# PixieChroma.net
KiCad netlist of a schematic drawn in EAGLE
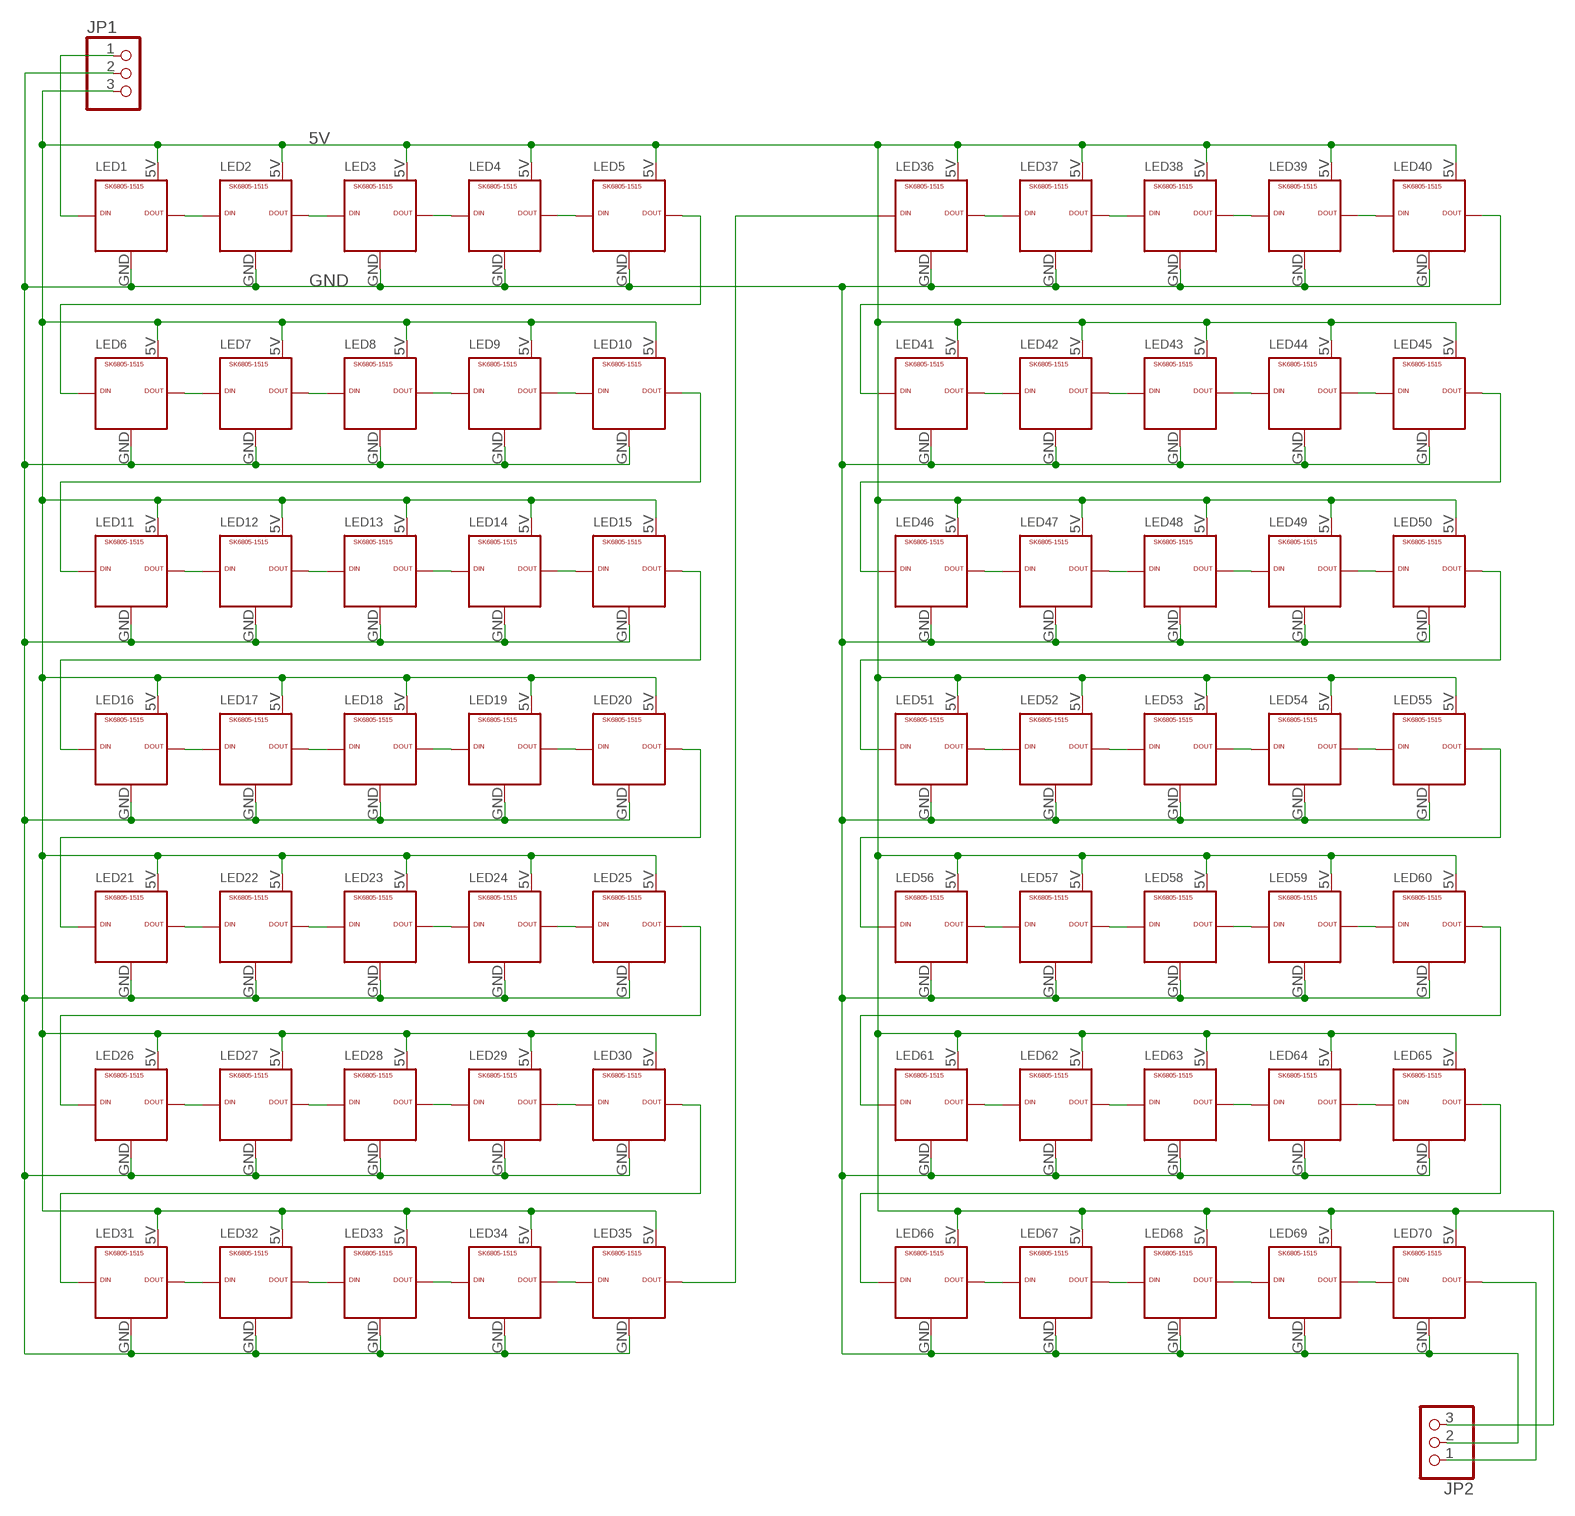
[diagram p0: schematic, sheet 1]

(export (version "E")
  (design (tool "Eeschema 10.0.6"))
  (components
    (comp (ref "JP1")
      (value "PINHD-1X3")
      (footprint "eagle-import:1X03")
      (libsource (lib "eagle-import") (part "PINHD-1X3"))
    )
    (comp (ref "JP2")
      (value "PINHD-1X3")
      (footprint "eagle-import:1X03")
      (libsource (lib "eagle-import") (part "PINHD-1X3"))
    )
    (comp (ref "LED1")
      (value "SK6805-1515")
      (footprint "eagle-import:1515")
      (libsource (lib "eagle-import") (part "SK6805-1515"))
    )
    (comp (ref "LED2")
      (value "SK6805-1515")
      (footprint "eagle-import:1515")
      (libsource (lib "eagle-import") (part "SK6805-1515"))
    )
    (comp (ref "LED3")
      (value "SK6805-1515")
      (footprint "eagle-import:1515")
      (libsource (lib "eagle-import") (part "SK6805-1515"))
    )
    (comp (ref "LED4")
      (value "SK6805-1515")
      (footprint "eagle-import:1515")
      (libsource (lib "eagle-import") (part "SK6805-1515"))
    )
    (comp (ref "LED5")
      (value "SK6805-1515")
      (footprint "eagle-import:1515")
      (libsource (lib "eagle-import") (part "SK6805-1515"))
    )
    (comp (ref "LED6")
      (value "SK6805-1515")
      (footprint "eagle-import:1515")
      (libsource (lib "eagle-import") (part "SK6805-1515"))
    )
    (comp (ref "LED7")
      (value "SK6805-1515")
      (footprint "eagle-import:1515")
      (libsource (lib "eagle-import") (part "SK6805-1515"))
    )
    (comp (ref "LED8")
      (value "SK6805-1515")
      (footprint "eagle-import:1515")
      (libsource (lib "eagle-import") (part "SK6805-1515"))
    )
    (comp (ref "LED9")
      (value "SK6805-1515")
      (footprint "eagle-import:1515")
      (libsource (lib "eagle-import") (part "SK6805-1515"))
    )
    (comp (ref "LED10")
      (value "SK6805-1515")
      (footprint "eagle-import:1515")
      (libsource (lib "eagle-import") (part "SK6805-1515"))
    )
    (comp (ref "LED11")
      (value "SK6805-1515")
      (footprint "eagle-import:1515")
      (libsource (lib "eagle-import") (part "SK6805-1515"))
    )
    (comp (ref "LED12")
      (value "SK6805-1515")
      (footprint "eagle-import:1515")
      (libsource (lib "eagle-import") (part "SK6805-1515"))
    )
    (comp (ref "LED13")
      (value "SK6805-1515")
      (footprint "eagle-import:1515")
      (libsource (lib "eagle-import") (part "SK6805-1515"))
    )
    (comp (ref "LED14")
      (value "SK6805-1515")
      (footprint "eagle-import:1515")
      (libsource (lib "eagle-import") (part "SK6805-1515"))
    )
    (comp (ref "LED15")
      (value "SK6805-1515")
      (footprint "eagle-import:1515")
      (libsource (lib "eagle-import") (part "SK6805-1515"))
    )
    (comp (ref "LED16")
      (value "SK6805-1515")
      (footprint "eagle-import:1515")
      (libsource (lib "eagle-import") (part "SK6805-1515"))
    )
    (comp (ref "LED17")
      (value "SK6805-1515")
      (footprint "eagle-import:1515")
      (libsource (lib "eagle-import") (part "SK6805-1515"))
    )
    (comp (ref "LED18")
      (value "SK6805-1515")
      (footprint "eagle-import:1515")
      (libsource (lib "eagle-import") (part "SK6805-1515"))
    )
    (comp (ref "LED19")
      (value "SK6805-1515")
      (footprint "eagle-import:1515")
      (libsource (lib "eagle-import") (part "SK6805-1515"))
    )
    (comp (ref "LED20")
      (value "SK6805-1515")
      (footprint "eagle-import:1515")
      (libsource (lib "eagle-import") (part "SK6805-1515"))
    )
    (comp (ref "LED21")
      (value "SK6805-1515")
      (footprint "eagle-import:1515")
      (libsource (lib "eagle-import") (part "SK6805-1515"))
    )
    (comp (ref "LED22")
      (value "SK6805-1515")
      (footprint "eagle-import:1515")
      (libsource (lib "eagle-import") (part "SK6805-1515"))
    )
    (comp (ref "LED23")
      (value "SK6805-1515")
      (footprint "eagle-import:1515")
      (libsource (lib "eagle-import") (part "SK6805-1515"))
    )
    (comp (ref "LED24")
      (value "SK6805-1515")
      (footprint "eagle-import:1515")
      (libsource (lib "eagle-import") (part "SK6805-1515"))
    )
    (comp (ref "LED25")
      (value "SK6805-1515")
      (footprint "eagle-import:1515")
      (libsource (lib "eagle-import") (part "SK6805-1515"))
    )
    (comp (ref "LED26")
      (value "SK6805-1515")
      (footprint "eagle-import:1515")
      (libsource (lib "eagle-import") (part "SK6805-1515"))
    )
    (comp (ref "LED27")
      (value "SK6805-1515")
      (footprint "eagle-import:1515")
      (libsource (lib "eagle-import") (part "SK6805-1515"))
    )
    (comp (ref "LED28")
      (value "SK6805-1515")
      (footprint "eagle-import:1515")
      (libsource (lib "eagle-import") (part "SK6805-1515"))
    )
    (comp (ref "LED29")
      (value "SK6805-1515")
      (footprint "eagle-import:1515")
      (libsource (lib "eagle-import") (part "SK6805-1515"))
    )
    (comp (ref "LED30")
      (value "SK6805-1515")
      (footprint "eagle-import:1515")
      (libsource (lib "eagle-import") (part "SK6805-1515"))
    )
    (comp (ref "LED31")
      (value "SK6805-1515")
      (footprint "eagle-import:1515")
      (libsource (lib "eagle-import") (part "SK6805-1515"))
    )
    (comp (ref "LED32")
      (value "SK6805-1515")
      (footprint "eagle-import:1515")
      (libsource (lib "eagle-import") (part "SK6805-1515"))
    )
    (comp (ref "LED33")
      (value "SK6805-1515")
      (footprint "eagle-import:1515")
      (libsource (lib "eagle-import") (part "SK6805-1515"))
    )
    (comp (ref "LED34")
      (value "SK6805-1515")
      (footprint "eagle-import:1515")
      (libsource (lib "eagle-import") (part "SK6805-1515"))
    )
    (comp (ref "LED35")
      (value "SK6805-1515")
      (footprint "eagle-import:1515")
      (libsource (lib "eagle-import") (part "SK6805-1515"))
    )
    (comp (ref "LED36")
      (value "SK6805-1515")
      (footprint "eagle-import:1515")
      (libsource (lib "eagle-import") (part "SK6805-1515"))
    )
    (comp (ref "LED37")
      (value "SK6805-1515")
      (footprint "eagle-import:1515")
      (libsource (lib "eagle-import") (part "SK6805-1515"))
    )
    (comp (ref "LED38")
      (value "SK6805-1515")
      (footprint "eagle-import:1515")
      (libsource (lib "eagle-import") (part "SK6805-1515"))
    )
    (comp (ref "LED39")
      (value "SK6805-1515")
      (footprint "eagle-import:1515")
      (libsource (lib "eagle-import") (part "SK6805-1515"))
    )
    (comp (ref "LED40")
      (value "SK6805-1515")
      (footprint "eagle-import:1515")
      (libsource (lib "eagle-import") (part "SK6805-1515"))
    )
    (comp (ref "LED41")
      (value "SK6805-1515")
      (footprint "eagle-import:1515")
      (libsource (lib "eagle-import") (part "SK6805-1515"))
    )
    (comp (ref "LED42")
      (value "SK6805-1515")
      (footprint "eagle-import:1515")
      (libsource (lib "eagle-import") (part "SK6805-1515"))
    )
    (comp (ref "LED43")
      (value "SK6805-1515")
      (footprint "eagle-import:1515")
      (libsource (lib "eagle-import") (part "SK6805-1515"))
    )
    (comp (ref "LED44")
      (value "SK6805-1515")
      (footprint "eagle-import:1515")
      (libsource (lib "eagle-import") (part "SK6805-1515"))
    )
    (comp (ref "LED45")
      (value "SK6805-1515")
      (footprint "eagle-import:1515")
      (libsource (lib "eagle-import") (part "SK6805-1515"))
    )
    (comp (ref "LED46")
      (value "SK6805-1515")
      (footprint "eagle-import:1515")
      (libsource (lib "eagle-import") (part "SK6805-1515"))
    )
    (comp (ref "LED47")
      (value "SK6805-1515")
      (footprint "eagle-import:1515")
      (libsource (lib "eagle-import") (part "SK6805-1515"))
    )
    (comp (ref "LED48")
      (value "SK6805-1515")
      (footprint "eagle-import:1515")
      (libsource (lib "eagle-import") (part "SK6805-1515"))
    )
    (comp (ref "LED49")
      (value "SK6805-1515")
      (footprint "eagle-import:1515")
      (libsource (lib "eagle-import") (part "SK6805-1515"))
    )
    (comp (ref "LED50")
      (value "SK6805-1515")
      (footprint "eagle-import:1515")
      (libsource (lib "eagle-import") (part "SK6805-1515"))
    )
    (comp (ref "LED51")
      (value "SK6805-1515")
      (footprint "eagle-import:1515")
      (libsource (lib "eagle-import") (part "SK6805-1515"))
    )
    (comp (ref "LED52")
      (value "SK6805-1515")
      (footprint "eagle-import:1515")
      (libsource (lib "eagle-import") (part "SK6805-1515"))
    )
    (comp (ref "LED53")
      (value "SK6805-1515")
      (footprint "eagle-import:1515")
      (libsource (lib "eagle-import") (part "SK6805-1515"))
    )
    (comp (ref "LED54")
      (value "SK6805-1515")
      (footprint "eagle-import:1515")
      (libsource (lib "eagle-import") (part "SK6805-1515"))
    )
    (comp (ref "LED55")
      (value "SK6805-1515")
      (footprint "eagle-import:1515")
      (libsource (lib "eagle-import") (part "SK6805-1515"))
    )
    (comp (ref "LED56")
      (value "SK6805-1515")
      (footprint "eagle-import:1515")
      (libsource (lib "eagle-import") (part "SK6805-1515"))
    )
    (comp (ref "LED57")
      (value "SK6805-1515")
      (footprint "eagle-import:1515")
      (libsource (lib "eagle-import") (part "SK6805-1515"))
    )
    (comp (ref "LED58")
      (value "SK6805-1515")
      (footprint "eagle-import:1515")
      (libsource (lib "eagle-import") (part "SK6805-1515"))
    )
    (comp (ref "LED59")
      (value "SK6805-1515")
      (footprint "eagle-import:1515")
      (libsource (lib "eagle-import") (part "SK6805-1515"))
    )
    (comp (ref "LED60")
      (value "SK6805-1515")
      (footprint "eagle-import:1515")
      (libsource (lib "eagle-import") (part "SK6805-1515"))
    )
    (comp (ref "LED61")
      (value "SK6805-1515")
      (footprint "eagle-import:1515")
      (libsource (lib "eagle-import") (part "SK6805-1515"))
    )
    (comp (ref "LED62")
      (value "SK6805-1515")
      (footprint "eagle-import:1515")
      (libsource (lib "eagle-import") (part "SK6805-1515"))
    )
    (comp (ref "LED63")
      (value "SK6805-1515")
      (footprint "eagle-import:1515")
      (libsource (lib "eagle-import") (part "SK6805-1515"))
    )
    (comp (ref "LED64")
      (value "SK6805-1515")
      (footprint "eagle-import:1515")
      (libsource (lib "eagle-import") (part "SK6805-1515"))
    )
    (comp (ref "LED65")
      (value "SK6805-1515")
      (footprint "eagle-import:1515")
      (libsource (lib "eagle-import") (part "SK6805-1515"))
    )
    (comp (ref "LED66")
      (value "SK6805-1515")
      (footprint "eagle-import:1515")
      (libsource (lib "eagle-import") (part "SK6805-1515"))
    )
    (comp (ref "LED67")
      (value "SK6805-1515")
      (footprint "eagle-import:1515")
      (libsource (lib "eagle-import") (part "SK6805-1515"))
    )
    (comp (ref "LED68")
      (value "SK6805-1515")
      (footprint "eagle-import:1515")
      (libsource (lib "eagle-import") (part "SK6805-1515"))
    )
    (comp (ref "LED69")
      (value "SK6805-1515")
      (footprint "eagle-import:1515")
      (libsource (lib "eagle-import") (part "SK6805-1515"))
    )
    (comp (ref "LED70")
      (value "SK6805-1515")
      (footprint "eagle-import:1515")
      (libsource (lib "eagle-import") (part "SK6805-1515"))
    )
  )
  (nets
    (net (code "1") (name "/5V") (class "Default")
      (node (ref "JP1") (pin "3") (pinfunction "3_3") (pintype "passive"))
      (node (ref "JP2") (pin "3") (pinfunction "3_3") (pintype "passive"))
      (node (ref "LED1") (pin "5V") (pinfunction "5V_5V") (pintype "power_in"))
      (node (ref "LED10") (pin "5V") (pinfunction "5V_5V") (pintype "power_in"))
      (node (ref "LED11") (pin "5V") (pinfunction "5V_5V") (pintype "power_in"))
      (node (ref "LED12") (pin "5V") (pinfunction "5V_5V") (pintype "power_in"))
      (node (ref "LED13") (pin "5V") (pinfunction "5V_5V") (pintype "power_in"))
      (node (ref "LED14") (pin "5V") (pinfunction "5V_5V") (pintype "power_in"))
      (node (ref "LED15") (pin "5V") (pinfunction "5V_5V") (pintype "power_in"))
      (node (ref "LED16") (pin "5V") (pinfunction "5V_5V") (pintype "power_in"))
      (node (ref "LED17") (pin "5V") (pinfunction "5V_5V") (pintype "power_in"))
      (node (ref "LED18") (pin "5V") (pinfunction "5V_5V") (pintype "power_in"))
      (node (ref "LED19") (pin "5V") (pinfunction "5V_5V") (pintype "power_in"))
      (node (ref "LED2") (pin "5V") (pinfunction "5V_5V") (pintype "power_in"))
      (node (ref "LED20") (pin "5V") (pinfunction "5V_5V") (pintype "power_in"))
      (node (ref "LED21") (pin "5V") (pinfunction "5V_5V") (pintype "power_in"))
      (node (ref "LED22") (pin "5V") (pinfunction "5V_5V") (pintype "power_in"))
      (node (ref "LED23") (pin "5V") (pinfunction "5V_5V") (pintype "power_in"))
      (node (ref "LED24") (pin "5V") (pinfunction "5V_5V") (pintype "power_in"))
      (node (ref "LED25") (pin "5V") (pinfunction "5V_5V") (pintype "power_in"))
      (node (ref "LED26") (pin "5V") (pinfunction "5V_5V") (pintype "power_in"))
      (node (ref "LED27") (pin "5V") (pinfunction "5V_5V") (pintype "power_in"))
      (node (ref "LED28") (pin "5V") (pinfunction "5V_5V") (pintype "power_in"))
      (node (ref "LED29") (pin "5V") (pinfunction "5V_5V") (pintype "power_in"))
      (node (ref "LED3") (pin "5V") (pinfunction "5V_5V") (pintype "power_in"))
      (node (ref "LED30") (pin "5V") (pinfunction "5V_5V") (pintype "power_in"))
      (node (ref "LED31") (pin "5V") (pinfunction "5V_5V") (pintype "power_in"))
      (node (ref "LED32") (pin "5V") (pinfunction "5V_5V") (pintype "power_in"))
      (node (ref "LED33") (pin "5V") (pinfunction "5V_5V") (pintype "power_in"))
      (node (ref "LED34") (pin "5V") (pinfunction "5V_5V") (pintype "power_in"))
      (node (ref "LED35") (pin "5V") (pinfunction "5V_5V") (pintype "power_in"))
      (node (ref "LED36") (pin "5V") (pinfunction "5V_5V") (pintype "power_in"))
      (node (ref "LED37") (pin "5V") (pinfunction "5V_5V") (pintype "power_in"))
      (node (ref "LED38") (pin "5V") (pinfunction "5V_5V") (pintype "power_in"))
      (node (ref "LED39") (pin "5V") (pinfunction "5V_5V") (pintype "power_in"))
      (node (ref "LED4") (pin "5V") (pinfunction "5V_5V") (pintype "power_in"))
      (node (ref "LED40") (pin "5V") (pinfunction "5V_5V") (pintype "power_in"))
      (node (ref "LED41") (pin "5V") (pinfunction "5V_5V") (pintype "power_in"))
      (node (ref "LED42") (pin "5V") (pinfunction "5V_5V") (pintype "power_in"))
      (node (ref "LED43") (pin "5V") (pinfunction "5V_5V") (pintype "power_in"))
      (node (ref "LED44") (pin "5V") (pinfunction "5V_5V") (pintype "power_in"))
      (node (ref "LED45") (pin "5V") (pinfunction "5V_5V") (pintype "power_in"))
      (node (ref "LED46") (pin "5V") (pinfunction "5V_5V") (pintype "power_in"))
      (node (ref "LED47") (pin "5V") (pinfunction "5V_5V") (pintype "power_in"))
      (node (ref "LED48") (pin "5V") (pinfunction "5V_5V") (pintype "power_in"))
      (node (ref "LED49") (pin "5V") (pinfunction "5V_5V") (pintype "power_in"))
      (node (ref "LED5") (pin "5V") (pinfunction "5V_5V") (pintype "power_in"))
      (node (ref "LED50") (pin "5V") (pinfunction "5V_5V") (pintype "power_in"))
      (node (ref "LED51") (pin "5V") (pinfunction "5V_5V") (pintype "power_in"))
      (node (ref "LED52") (pin "5V") (pinfunction "5V_5V") (pintype "power_in"))
      (node (ref "LED53") (pin "5V") (pinfunction "5V_5V") (pintype "power_in"))
      (node (ref "LED54") (pin "5V") (pinfunction "5V_5V") (pintype "power_in"))
      (node (ref "LED55") (pin "5V") (pinfunction "5V_5V") (pintype "power_in"))
      (node (ref "LED56") (pin "5V") (pinfunction "5V_5V") (pintype "power_in"))
      (node (ref "LED57") (pin "5V") (pinfunction "5V_5V") (pintype "power_in"))
      (node (ref "LED58") (pin "5V") (pinfunction "5V_5V") (pintype "power_in"))
      (node (ref "LED59") (pin "5V") (pinfunction "5V_5V") (pintype "power_in"))
      (node (ref "LED6") (pin "5V") (pinfunction "5V_5V") (pintype "power_in"))
      (node (ref "LED60") (pin "5V") (pinfunction "5V_5V") (pintype "power_in"))
      (node (ref "LED61") (pin "5V") (pinfunction "5V_5V") (pintype "power_in"))
      (node (ref "LED62") (pin "5V") (pinfunction "5V_5V") (pintype "power_in"))
      (node (ref "LED63") (pin "5V") (pinfunction "5V_5V") (pintype "power_in"))
      (node (ref "LED64") (pin "5V") (pinfunction "5V_5V") (pintype "power_in"))
      (node (ref "LED65") (pin "5V") (pinfunction "5V_5V") (pintype "power_in"))
      (node (ref "LED66") (pin "5V") (pinfunction "5V_5V") (pintype "power_in"))
      (node (ref "LED67") (pin "5V") (pinfunction "5V_5V") (pintype "power_in"))
      (node (ref "LED68") (pin "5V") (pinfunction "5V_5V") (pintype "power_in"))
      (node (ref "LED69") (pin "5V") (pinfunction "5V_5V") (pintype "power_in"))
      (node (ref "LED7") (pin "5V") (pinfunction "5V_5V") (pintype "power_in"))
      (node (ref "LED70") (pin "5V") (pinfunction "5V_5V") (pintype "power_in"))
      (node (ref "LED8") (pin "5V") (pinfunction "5V_5V") (pintype "power_in"))
      (node (ref "LED9") (pin "5V") (pinfunction "5V_5V") (pintype "power_in"))
    )
    (net (code "2") (name "/GND") (class "Default")
      (node (ref "JP1") (pin "2") (pinfunction "2_2") (pintype "passive"))
      (node (ref "JP2") (pin "2") (pinfunction "2_2") (pintype "passive"))
      (node (ref "LED1") (pin "GND") (pinfunction "GND_GND") (pintype "power_in"))
      (node (ref "LED10") (pin "GND") (pinfunction "GND_GND") (pintype "power_in"))
      (node (ref "LED11") (pin "GND") (pinfunction "GND_GND") (pintype "power_in"))
      (node (ref "LED12") (pin "GND") (pinfunction "GND_GND") (pintype "power_in"))
      (node (ref "LED13") (pin "GND") (pinfunction "GND_GND") (pintype "power_in"))
      (node (ref "LED14") (pin "GND") (pinfunction "GND_GND") (pintype "power_in"))
      (node (ref "LED15") (pin "GND") (pinfunction "GND_GND") (pintype "power_in"))
      (node (ref "LED16") (pin "GND") (pinfunction "GND_GND") (pintype "power_in"))
      (node (ref "LED17") (pin "GND") (pinfunction "GND_GND") (pintype "power_in"))
      (node (ref "LED18") (pin "GND") (pinfunction "GND_GND") (pintype "power_in"))
      (node (ref "LED19") (pin "GND") (pinfunction "GND_GND") (pintype "power_in"))
      (node (ref "LED2") (pin "GND") (pinfunction "GND_GND") (pintype "power_in"))
      (node (ref "LED20") (pin "GND") (pinfunction "GND_GND") (pintype "power_in"))
      (node (ref "LED21") (pin "GND") (pinfunction "GND_GND") (pintype "power_in"))
      (node (ref "LED22") (pin "GND") (pinfunction "GND_GND") (pintype "power_in"))
      (node (ref "LED23") (pin "GND") (pinfunction "GND_GND") (pintype "power_in"))
      (node (ref "LED24") (pin "GND") (pinfunction "GND_GND") (pintype "power_in"))
      (node (ref "LED25") (pin "GND") (pinfunction "GND_GND") (pintype "power_in"))
      (node (ref "LED26") (pin "GND") (pinfunction "GND_GND") (pintype "power_in"))
      (node (ref "LED27") (pin "GND") (pinfunction "GND_GND") (pintype "power_in"))
      (node (ref "LED28") (pin "GND") (pinfunction "GND_GND") (pintype "power_in"))
      (node (ref "LED29") (pin "GND") (pinfunction "GND_GND") (pintype "power_in"))
      (node (ref "LED3") (pin "GND") (pinfunction "GND_GND") (pintype "power_in"))
      (node (ref "LED30") (pin "GND") (pinfunction "GND_GND") (pintype "power_in"))
      (node (ref "LED31") (pin "GND") (pinfunction "GND_GND") (pintype "power_in"))
      (node (ref "LED32") (pin "GND") (pinfunction "GND_GND") (pintype "power_in"))
      (node (ref "LED33") (pin "GND") (pinfunction "GND_GND") (pintype "power_in"))
      (node (ref "LED34") (pin "GND") (pinfunction "GND_GND") (pintype "power_in"))
      (node (ref "LED35") (pin "GND") (pinfunction "GND_GND") (pintype "power_in"))
      (node (ref "LED36") (pin "GND") (pinfunction "GND_GND") (pintype "power_in"))
      (node (ref "LED37") (pin "GND") (pinfunction "GND_GND") (pintype "power_in"))
      (node (ref "LED38") (pin "GND") (pinfunction "GND_GND") (pintype "power_in"))
      (node (ref "LED39") (pin "GND") (pinfunction "GND_GND") (pintype "power_in"))
      (node (ref "LED4") (pin "GND") (pinfunction "GND_GND") (pintype "power_in"))
      (node (ref "LED40") (pin "GND") (pinfunction "GND_GND") (pintype "power_in"))
      (node (ref "LED41") (pin "GND") (pinfunction "GND_GND") (pintype "power_in"))
      (node (ref "LED42") (pin "GND") (pinfunction "GND_GND") (pintype "power_in"))
      (node (ref "LED43") (pin "GND") (pinfunction "GND_GND") (pintype "power_in"))
      (node (ref "LED44") (pin "GND") (pinfunction "GND_GND") (pintype "power_in"))
      (node (ref "LED45") (pin "GND") (pinfunction "GND_GND") (pintype "power_in"))
      (node (ref "LED46") (pin "GND") (pinfunction "GND_GND") (pintype "power_in"))
      (node (ref "LED47") (pin "GND") (pinfunction "GND_GND") (pintype "power_in"))
      (node (ref "LED48") (pin "GND") (pinfunction "GND_GND") (pintype "power_in"))
      (node (ref "LED49") (pin "GND") (pinfunction "GND_GND") (pintype "power_in"))
      (node (ref "LED5") (pin "GND") (pinfunction "GND_GND") (pintype "power_in"))
      (node (ref "LED50") (pin "GND") (pinfunction "GND_GND") (pintype "power_in"))
      (node (ref "LED51") (pin "GND") (pinfunction "GND_GND") (pintype "power_in"))
      (node (ref "LED52") (pin "GND") (pinfunction "GND_GND") (pintype "power_in"))
      (node (ref "LED53") (pin "GND") (pinfunction "GND_GND") (pintype "power_in"))
      (node (ref "LED54") (pin "GND") (pinfunction "GND_GND") (pintype "power_in"))
      (node (ref "LED55") (pin "GND") (pinfunction "GND_GND") (pintype "power_in"))
      (node (ref "LED56") (pin "GND") (pinfunction "GND_GND") (pintype "power_in"))
      (node (ref "LED57") (pin "GND") (pinfunction "GND_GND") (pintype "power_in"))
      (node (ref "LED58") (pin "GND") (pinfunction "GND_GND") (pintype "power_in"))
      (node (ref "LED59") (pin "GND") (pinfunction "GND_GND") (pintype "power_in"))
      (node (ref "LED6") (pin "GND") (pinfunction "GND_GND") (pintype "power_in"))
      (node (ref "LED60") (pin "GND") (pinfunction "GND_GND") (pintype "power_in"))
      (node (ref "LED61") (pin "GND") (pinfunction "GND_GND") (pintype "power_in"))
      (node (ref "LED62") (pin "GND") (pinfunction "GND_GND") (pintype "power_in"))
      (node (ref "LED63") (pin "GND") (pinfunction "GND_GND") (pintype "power_in"))
      (node (ref "LED64") (pin "GND") (pinfunction "GND_GND") (pintype "power_in"))
      (node (ref "LED65") (pin "GND") (pinfunction "GND_GND") (pintype "power_in"))
      (node (ref "LED66") (pin "GND") (pinfunction "GND_GND") (pintype "power_in"))
      (node (ref "LED67") (pin "GND") (pinfunction "GND_GND") (pintype "power_in"))
      (node (ref "LED68") (pin "GND") (pinfunction "GND_GND") (pintype "power_in"))
      (node (ref "LED69") (pin "GND") (pinfunction "GND_GND") (pintype "power_in"))
      (node (ref "LED7") (pin "GND") (pinfunction "GND_GND") (pintype "power_in"))
      (node (ref "LED70") (pin "GND") (pinfunction "GND_GND") (pintype "power_in"))
      (node (ref "LED8") (pin "GND") (pinfunction "GND_GND") (pintype "power_in"))
      (node (ref "LED9") (pin "GND") (pinfunction "GND_GND") (pintype "power_in"))
    )
    (net (code "3") (name "Net-(JP1-Pad1)") (class "Default")
      (node (ref "JP1") (pin "1") (pinfunction "1_1") (pintype "passive"))
      (node (ref "LED1") (pin "DIN") (pinfunction "DIN_DIN") (pintype "bidirectional"))
    )
    (net (code "4") (name "Net-(JP2-Pad1)") (class "Default")
      (node (ref "JP2") (pin "1") (pinfunction "1_1") (pintype "passive"))
      (node (ref "LED70") (pin "DOUT") (pinfunction "DOUT_DOUT") (pintype "bidirectional"))
    )
    (net (code "5") (name "Net-(LED1-PadDOUT)") (class "Default")
      (node (ref "LED1") (pin "DOUT") (pinfunction "DOUT_DOUT") (pintype "bidirectional"))
      (node (ref "LED2") (pin "DIN") (pinfunction "DIN_DIN") (pintype "bidirectional"))
    )
    (net (code "6") (name "Net-(LED2-PadDOUT)") (class "Default")
      (node (ref "LED2") (pin "DOUT") (pinfunction "DOUT_DOUT") (pintype "bidirectional"))
      (node (ref "LED3") (pin "DIN") (pinfunction "DIN_DIN") (pintype "bidirectional"))
    )
    (net (code "7") (name "Net-(LED3-PadDOUT)") (class "Default")
      (node (ref "LED3") (pin "DOUT") (pinfunction "DOUT_DOUT") (pintype "bidirectional"))
      (node (ref "LED4") (pin "DIN") (pinfunction "DIN_DIN") (pintype "bidirectional"))
    )
    (net (code "8") (name "Net-(LED4-PadDOUT)") (class "Default")
      (node (ref "LED4") (pin "DOUT") (pinfunction "DOUT_DOUT") (pintype "bidirectional"))
      (node (ref "LED5") (pin "DIN") (pinfunction "DIN_DIN") (pintype "bidirectional"))
    )
    (net (code "9") (name "Net-(LED5-PadDOUT)") (class "Default")
      (node (ref "LED5") (pin "DOUT") (pinfunction "DOUT_DOUT") (pintype "bidirectional"))
      (node (ref "LED6") (pin "DIN") (pinfunction "DIN_DIN") (pintype "bidirectional"))
    )
    (net (code "10") (name "Net-(LED6-PadDOUT)") (class "Default")
      (node (ref "LED6") (pin "DOUT") (pinfunction "DOUT_DOUT") (pintype "bidirectional"))
      (node (ref "LED7") (pin "DIN") (pinfunction "DIN_DIN") (pintype "bidirectional"))
    )
    (net (code "11") (name "Net-(LED7-PadDOUT)") (class "Default")
      (node (ref "LED7") (pin "DOUT") (pinfunction "DOUT_DOUT") (pintype "bidirectional"))
      (node (ref "LED8") (pin "DIN") (pinfunction "DIN_DIN") (pintype "bidirectional"))
    )
    (net (code "12") (name "Net-(LED8-PadDOUT)") (class "Default")
      (node (ref "LED8") (pin "DOUT") (pinfunction "DOUT_DOUT") (pintype "bidirectional"))
      (node (ref "LED9") (pin "DIN") (pinfunction "DIN_DIN") (pintype "bidirectional"))
    )
    (net (code "13") (name "Net-(LED10-PadDIN)") (class "Default")
      (node (ref "LED10") (pin "DIN") (pinfunction "DIN_DIN") (pintype "bidirectional"))
      (node (ref "LED9") (pin "DOUT") (pinfunction "DOUT_DOUT") (pintype "bidirectional"))
    )
    (net (code "14") (name "Net-(LED10-PadDOUT)") (class "Default")
      (node (ref "LED10") (pin "DOUT") (pinfunction "DOUT_DOUT") (pintype "bidirectional"))
      (node (ref "LED11") (pin "DIN") (pinfunction "DIN_DIN") (pintype "bidirectional"))
    )
    (net (code "15") (name "Net-(LED11-PadDOUT)") (class "Default")
      (node (ref "LED11") (pin "DOUT") (pinfunction "DOUT_DOUT") (pintype "bidirectional"))
      (node (ref "LED12") (pin "DIN") (pinfunction "DIN_DIN") (pintype "bidirectional"))
    )
    (net (code "16") (name "Net-(LED12-PadDOUT)") (class "Default")
      (node (ref "LED12") (pin "DOUT") (pinfunction "DOUT_DOUT") (pintype "bidirectional"))
      (node (ref "LED13") (pin "DIN") (pinfunction "DIN_DIN") (pintype "bidirectional"))
    )
    (net (code "17") (name "Net-(LED13-PadDOUT)") (class "Default")
      (node (ref "LED13") (pin "DOUT") (pinfunction "DOUT_DOUT") (pintype "bidirectional"))
      (node (ref "LED14") (pin "DIN") (pinfunction "DIN_DIN") (pintype "bidirectional"))
    )
    (net (code "18") (name "Net-(LED14-PadDOUT)") (class "Default")
      (node (ref "LED14") (pin "DOUT") (pinfunction "DOUT_DOUT") (pintype "bidirectional"))
      (node (ref "LED15") (pin "DIN") (pinfunction "DIN_DIN") (pintype "bidirectional"))
    )
    (net (code "19") (name "Net-(LED15-PadDOUT)") (class "Default")
      (node (ref "LED15") (pin "DOUT") (pinfunction "DOUT_DOUT") (pintype "bidirectional"))
      (node (ref "LED16") (pin "DIN") (pinfunction "DIN_DIN") (pintype "bidirectional"))
    )
    (net (code "20") (name "Net-(LED16-PadDOUT)") (class "Default")
      (node (ref "LED16") (pin "DOUT") (pinfunction "DOUT_DOUT") (pintype "bidirectional"))
      (node (ref "LED17") (pin "DIN") (pinfunction "DIN_DIN") (pintype "bidirectional"))
    )
    (net (code "21") (name "Net-(LED17-PadDOUT)") (class "Default")
      (node (ref "LED17") (pin "DOUT") (pinfunction "DOUT_DOUT") (pintype "bidirectional"))
      (node (ref "LED18") (pin "DIN") (pinfunction "DIN_DIN") (pintype "bidirectional"))
    )
    (net (code "22") (name "Net-(LED18-PadDOUT)") (class "Default")
      (node (ref "LED18") (pin "DOUT") (pinfunction "DOUT_DOUT") (pintype "bidirectional"))
      (node (ref "LED19") (pin "DIN") (pinfunction "DIN_DIN") (pintype "bidirectional"))
    )
    (net (code "23") (name "Net-(LED19-PadDOUT)") (class "Default")
      (node (ref "LED19") (pin "DOUT") (pinfunction "DOUT_DOUT") (pintype "bidirectional"))
      (node (ref "LED20") (pin "DIN") (pinfunction "DIN_DIN") (pintype "bidirectional"))
    )
    (net (code "24") (name "Net-(LED20-PadDOUT)") (class "Default")
      (node (ref "LED20") (pin "DOUT") (pinfunction "DOUT_DOUT") (pintype "bidirectional"))
      (node (ref "LED21") (pin "DIN") (pinfunction "DIN_DIN") (pintype "bidirectional"))
    )
    (net (code "25") (name "Net-(LED21-PadDOUT)") (class "Default")
      (node (ref "LED21") (pin "DOUT") (pinfunction "DOUT_DOUT") (pintype "bidirectional"))
      (node (ref "LED22") (pin "DIN") (pinfunction "DIN_DIN") (pintype "bidirectional"))
    )
    (net (code "26") (name "Net-(LED22-PadDOUT)") (class "Default")
      (node (ref "LED22") (pin "DOUT") (pinfunction "DOUT_DOUT") (pintype "bidirectional"))
      (node (ref "LED23") (pin "DIN") (pinfunction "DIN_DIN") (pintype "bidirectional"))
    )
    (net (code "27") (name "Net-(LED23-PadDOUT)") (class "Default")
      (node (ref "LED23") (pin "DOUT") (pinfunction "DOUT_DOUT") (pintype "bidirectional"))
      (node (ref "LED24") (pin "DIN") (pinfunction "DIN_DIN") (pintype "bidirectional"))
    )
    (net (code "28") (name "Net-(LED24-PadDOUT)") (class "Default")
      (node (ref "LED24") (pin "DOUT") (pinfunction "DOUT_DOUT") (pintype "bidirectional"))
      (node (ref "LED25") (pin "DIN") (pinfunction "DIN_DIN") (pintype "bidirectional"))
    )
    (net (code "29") (name "Net-(LED25-PadDOUT)") (class "Default")
      (node (ref "LED25") (pin "DOUT") (pinfunction "DOUT_DOUT") (pintype "bidirectional"))
      (node (ref "LED26") (pin "DIN") (pinfunction "DIN_DIN") (pintype "bidirectional"))
    )
    (net (code "30") (name "Net-(LED26-PadDOUT)") (class "Default")
      (node (ref "LED26") (pin "DOUT") (pinfunction "DOUT_DOUT") (pintype "bidirectional"))
      (node (ref "LED27") (pin "DIN") (pinfunction "DIN_DIN") (pintype "bidirectional"))
    )
    (net (code "31") (name "Net-(LED27-PadDOUT)") (class "Default")
      (node (ref "LED27") (pin "DOUT") (pinfunction "DOUT_DOUT") (pintype "bidirectional"))
      (node (ref "LED28") (pin "DIN") (pinfunction "DIN_DIN") (pintype "bidirectional"))
    )
    (net (code "32") (name "Net-(LED28-PadDOUT)") (class "Default")
      (node (ref "LED28") (pin "DOUT") (pinfunction "DOUT_DOUT") (pintype "bidirectional"))
      (node (ref "LED29") (pin "DIN") (pinfunction "DIN_DIN") (pintype "bidirectional"))
    )
    (net (code "33") (name "Net-(LED29-PadDOUT)") (class "Default")
      (node (ref "LED29") (pin "DOUT") (pinfunction "DOUT_DOUT") (pintype "bidirectional"))
      (node (ref "LED30") (pin "DIN") (pinfunction "DIN_DIN") (pintype "bidirectional"))
    )
    (net (code "34") (name "Net-(LED30-PadDOUT)") (class "Default")
      (node (ref "LED30") (pin "DOUT") (pinfunction "DOUT_DOUT") (pintype "bidirectional"))
      (node (ref "LED31") (pin "DIN") (pinfunction "DIN_DIN") (pintype "bidirectional"))
    )
    (net (code "35") (name "Net-(LED31-PadDOUT)") (class "Default")
      (node (ref "LED31") (pin "DOUT") (pinfunction "DOUT_DOUT") (pintype "bidirectional"))
      (node (ref "LED32") (pin "DIN") (pinfunction "DIN_DIN") (pintype "bidirectional"))
    )
    (net (code "36") (name "Net-(LED32-PadDOUT)") (class "Default")
      (node (ref "LED32") (pin "DOUT") (pinfunction "DOUT_DOUT") (pintype "bidirectional"))
      (node (ref "LED33") (pin "DIN") (pinfunction "DIN_DIN") (pintype "bidirectional"))
    )
    (net (code "37") (name "Net-(LED33-PadDOUT)") (class "Default")
      (node (ref "LED33") (pin "DOUT") (pinfunction "DOUT_DOUT") (pintype "bidirectional"))
      (node (ref "LED34") (pin "DIN") (pinfunction "DIN_DIN") (pintype "bidirectional"))
    )
    (net (code "38") (name "Net-(LED34-PadDOUT)") (class "Default")
      (node (ref "LED34") (pin "DOUT") (pinfunction "DOUT_DOUT") (pintype "bidirectional"))
      (node (ref "LED35") (pin "DIN") (pinfunction "DIN_DIN") (pintype "bidirectional"))
    )
    (net (code "39") (name "Net-(LED35-PadDOUT)") (class "Default")
      (node (ref "LED35") (pin "DOUT") (pinfunction "DOUT_DOUT") (pintype "bidirectional"))
      (node (ref "LED36") (pin "DIN") (pinfunction "DIN_DIN") (pintype "bidirectional"))
    )
    (net (code "40") (name "Net-(LED36-PadDOUT)") (class "Default")
      (node (ref "LED36") (pin "DOUT") (pinfunction "DOUT_DOUT") (pintype "bidirectional"))
      (node (ref "LED37") (pin "DIN") (pinfunction "DIN_DIN") (pintype "bidirectional"))
    )
    (net (code "41") (name "Net-(LED37-PadDOUT)") (class "Default")
      (node (ref "LED37") (pin "DOUT") (pinfunction "DOUT_DOUT") (pintype "bidirectional"))
      (node (ref "LED38") (pin "DIN") (pinfunction "DIN_DIN") (pintype "bidirectional"))
    )
    (net (code "42") (name "Net-(LED38-PadDOUT)") (class "Default")
      (node (ref "LED38") (pin "DOUT") (pinfunction "DOUT_DOUT") (pintype "bidirectional"))
      (node (ref "LED39") (pin "DIN") (pinfunction "DIN_DIN") (pintype "bidirectional"))
    )
    (net (code "43") (name "Net-(LED39-PadDOUT)") (class "Default")
      (node (ref "LED39") (pin "DOUT") (pinfunction "DOUT_DOUT") (pintype "bidirectional"))
      (node (ref "LED40") (pin "DIN") (pinfunction "DIN_DIN") (pintype "bidirectional"))
    )
    (net (code "44") (name "Net-(LED40-PadDOUT)") (class "Default")
      (node (ref "LED40") (pin "DOUT") (pinfunction "DOUT_DOUT") (pintype "bidirectional"))
      (node (ref "LED41") (pin "DIN") (pinfunction "DIN_DIN") (pintype "bidirectional"))
    )
    (net (code "45") (name "Net-(LED41-PadDOUT)") (class "Default")
      (node (ref "LED41") (pin "DOUT") (pinfunction "DOUT_DOUT") (pintype "bidirectional"))
      (node (ref "LED42") (pin "DIN") (pinfunction "DIN_DIN") (pintype "bidirectional"))
    )
    (net (code "46") (name "Net-(LED42-PadDOUT)") (class "Default")
      (node (ref "LED42") (pin "DOUT") (pinfunction "DOUT_DOUT") (pintype "bidirectional"))
      (node (ref "LED43") (pin "DIN") (pinfunction "DIN_DIN") (pintype "bidirectional"))
    )
    (net (code "47") (name "Net-(LED43-PadDOUT)") (class "Default")
      (node (ref "LED43") (pin "DOUT") (pinfunction "DOUT_DOUT") (pintype "bidirectional"))
      (node (ref "LED44") (pin "DIN") (pinfunction "DIN_DIN") (pintype "bidirectional"))
    )
    (net (code "48") (name "Net-(LED44-PadDOUT)") (class "Default")
      (node (ref "LED44") (pin "DOUT") (pinfunction "DOUT_DOUT") (pintype "bidirectional"))
      (node (ref "LED45") (pin "DIN") (pinfunction "DIN_DIN") (pintype "bidirectional"))
    )
    (net (code "49") (name "Net-(LED45-PadDOUT)") (class "Default")
      (node (ref "LED45") (pin "DOUT") (pinfunction "DOUT_DOUT") (pintype "bidirectional"))
      (node (ref "LED46") (pin "DIN") (pinfunction "DIN_DIN") (pintype "bidirectional"))
    )
    (net (code "50") (name "Net-(LED46-PadDOUT)") (class "Default")
      (node (ref "LED46") (pin "DOUT") (pinfunction "DOUT_DOUT") (pintype "bidirectional"))
      (node (ref "LED47") (pin "DIN") (pinfunction "DIN_DIN") (pintype "bidirectional"))
    )
    (net (code "51") (name "Net-(LED47-PadDOUT)") (class "Default")
      (node (ref "LED47") (pin "DOUT") (pinfunction "DOUT_DOUT") (pintype "bidirectional"))
      (node (ref "LED48") (pin "DIN") (pinfunction "DIN_DIN") (pintype "bidirectional"))
    )
    (net (code "52") (name "Net-(LED48-PadDOUT)") (class "Default")
      (node (ref "LED48") (pin "DOUT") (pinfunction "DOUT_DOUT") (pintype "bidirectional"))
      (node (ref "LED49") (pin "DIN") (pinfunction "DIN_DIN") (pintype "bidirectional"))
    )
    (net (code "53") (name "Net-(LED49-PadDOUT)") (class "Default")
      (node (ref "LED49") (pin "DOUT") (pinfunction "DOUT_DOUT") (pintype "bidirectional"))
      (node (ref "LED50") (pin "DIN") (pinfunction "DIN_DIN") (pintype "bidirectional"))
    )
    (net (code "54") (name "Net-(LED50-PadDOUT)") (class "Default")
      (node (ref "LED50") (pin "DOUT") (pinfunction "DOUT_DOUT") (pintype "bidirectional"))
      (node (ref "LED51") (pin "DIN") (pinfunction "DIN_DIN") (pintype "bidirectional"))
    )
    (net (code "55") (name "Net-(LED51-PadDOUT)") (class "Default")
      (node (ref "LED51") (pin "DOUT") (pinfunction "DOUT_DOUT") (pintype "bidirectional"))
      (node (ref "LED52") (pin "DIN") (pinfunction "DIN_DIN") (pintype "bidirectional"))
    )
    (net (code "56") (name "Net-(LED52-PadDOUT)") (class "Default")
      (node (ref "LED52") (pin "DOUT") (pinfunction "DOUT_DOUT") (pintype "bidirectional"))
      (node (ref "LED53") (pin "DIN") (pinfunction "DIN_DIN") (pintype "bidirectional"))
    )
    (net (code "57") (name "Net-(LED53-PadDOUT)") (class "Default")
      (node (ref "LED53") (pin "DOUT") (pinfunction "DOUT_DOUT") (pintype "bidirectional"))
      (node (ref "LED54") (pin "DIN") (pinfunction "DIN_DIN") (pintype "bidirectional"))
    )
    (net (code "58") (name "Net-(LED54-PadDOUT)") (class "Default")
      (node (ref "LED54") (pin "DOUT") (pinfunction "DOUT_DOUT") (pintype "bidirectional"))
      (node (ref "LED55") (pin "DIN") (pinfunction "DIN_DIN") (pintype "bidirectional"))
    )
    (net (code "59") (name "Net-(LED55-PadDOUT)") (class "Default")
      (node (ref "LED55") (pin "DOUT") (pinfunction "DOUT_DOUT") (pintype "bidirectional"))
      (node (ref "LED56") (pin "DIN") (pinfunction "DIN_DIN") (pintype "bidirectional"))
    )
    (net (code "60") (name "Net-(LED56-PadDOUT)") (class "Default")
      (node (ref "LED56") (pin "DOUT") (pinfunction "DOUT_DOUT") (pintype "bidirectional"))
      (node (ref "LED57") (pin "DIN") (pinfunction "DIN_DIN") (pintype "bidirectional"))
    )
    (net (code "61") (name "Net-(LED57-PadDOUT)") (class "Default")
      (node (ref "LED57") (pin "DOUT") (pinfunction "DOUT_DOUT") (pintype "bidirectional"))
      (node (ref "LED58") (pin "DIN") (pinfunction "DIN_DIN") (pintype "bidirectional"))
    )
    (net (code "62") (name "Net-(LED58-PadDOUT)") (class "Default")
      (node (ref "LED58") (pin "DOUT") (pinfunction "DOUT_DOUT") (pintype "bidirectional"))
      (node (ref "LED59") (pin "DIN") (pinfunction "DIN_DIN") (pintype "bidirectional"))
    )
    (net (code "63") (name "Net-(LED59-PadDOUT)") (class "Default")
      (node (ref "LED59") (pin "DOUT") (pinfunction "DOUT_DOUT") (pintype "bidirectional"))
      (node (ref "LED60") (pin "DIN") (pinfunction "DIN_DIN") (pintype "bidirectional"))
    )
    (net (code "64") (name "Net-(LED60-PadDOUT)") (class "Default")
      (node (ref "LED60") (pin "DOUT") (pinfunction "DOUT_DOUT") (pintype "bidirectional"))
      (node (ref "LED61") (pin "DIN") (pinfunction "DIN_DIN") (pintype "bidirectional"))
    )
    (net (code "65") (name "Net-(LED61-PadDOUT)") (class "Default")
      (node (ref "LED61") (pin "DOUT") (pinfunction "DOUT_DOUT") (pintype "bidirectional"))
      (node (ref "LED62") (pin "DIN") (pinfunction "DIN_DIN") (pintype "bidirectional"))
    )
    (net (code "66") (name "Net-(LED62-PadDOUT)") (class "Default")
      (node (ref "LED62") (pin "DOUT") (pinfunction "DOUT_DOUT") (pintype "bidirectional"))
      (node (ref "LED63") (pin "DIN") (pinfunction "DIN_DIN") (pintype "bidirectional"))
    )
    (net (code "67") (name "Net-(LED63-PadDOUT)") (class "Default")
      (node (ref "LED63") (pin "DOUT") (pinfunction "DOUT_DOUT") (pintype "bidirectional"))
      (node (ref "LED64") (pin "DIN") (pinfunction "DIN_DIN") (pintype "bidirectional"))
    )
    (net (code "68") (name "Net-(LED64-PadDOUT)") (class "Default")
      (node (ref "LED64") (pin "DOUT") (pinfunction "DOUT_DOUT") (pintype "bidirectional"))
      (node (ref "LED65") (pin "DIN") (pinfunction "DIN_DIN") (pintype "bidirectional"))
    )
    (net (code "69") (name "Net-(LED65-PadDOUT)") (class "Default")
      (node (ref "LED65") (pin "DOUT") (pinfunction "DOUT_DOUT") (pintype "bidirectional"))
      (node (ref "LED66") (pin "DIN") (pinfunction "DIN_DIN") (pintype "bidirectional"))
    )
    (net (code "70") (name "Net-(LED66-PadDOUT)") (class "Default")
      (node (ref "LED66") (pin "DOUT") (pinfunction "DOUT_DOUT") (pintype "bidirectional"))
      (node (ref "LED67") (pin "DIN") (pinfunction "DIN_DIN") (pintype "bidirectional"))
    )
    (net (code "71") (name "Net-(LED67-PadDOUT)") (class "Default")
      (node (ref "LED67") (pin "DOUT") (pinfunction "DOUT_DOUT") (pintype "bidirectional"))
      (node (ref "LED68") (pin "DIN") (pinfunction "DIN_DIN") (pintype "bidirectional"))
    )
    (net (code "72") (name "Net-(LED68-PadDOUT)") (class "Default")
      (node (ref "LED68") (pin "DOUT") (pinfunction "DOUT_DOUT") (pintype "bidirectional"))
      (node (ref "LED69") (pin "DIN") (pinfunction "DIN_DIN") (pintype "bidirectional"))
    )
    (net (code "73") (name "Net-(LED69-PadDOUT)") (class "Default")
      (node (ref "LED69") (pin "DOUT") (pinfunction "DOUT_DOUT") (pintype "bidirectional"))
      (node (ref "LED70") (pin "DIN") (pinfunction "DIN_DIN") (pintype "bidirectional"))
    )
  )
)
